# 4Z_PCB_2.net
KiCad netlist of a schematic drawn in Altium Designer
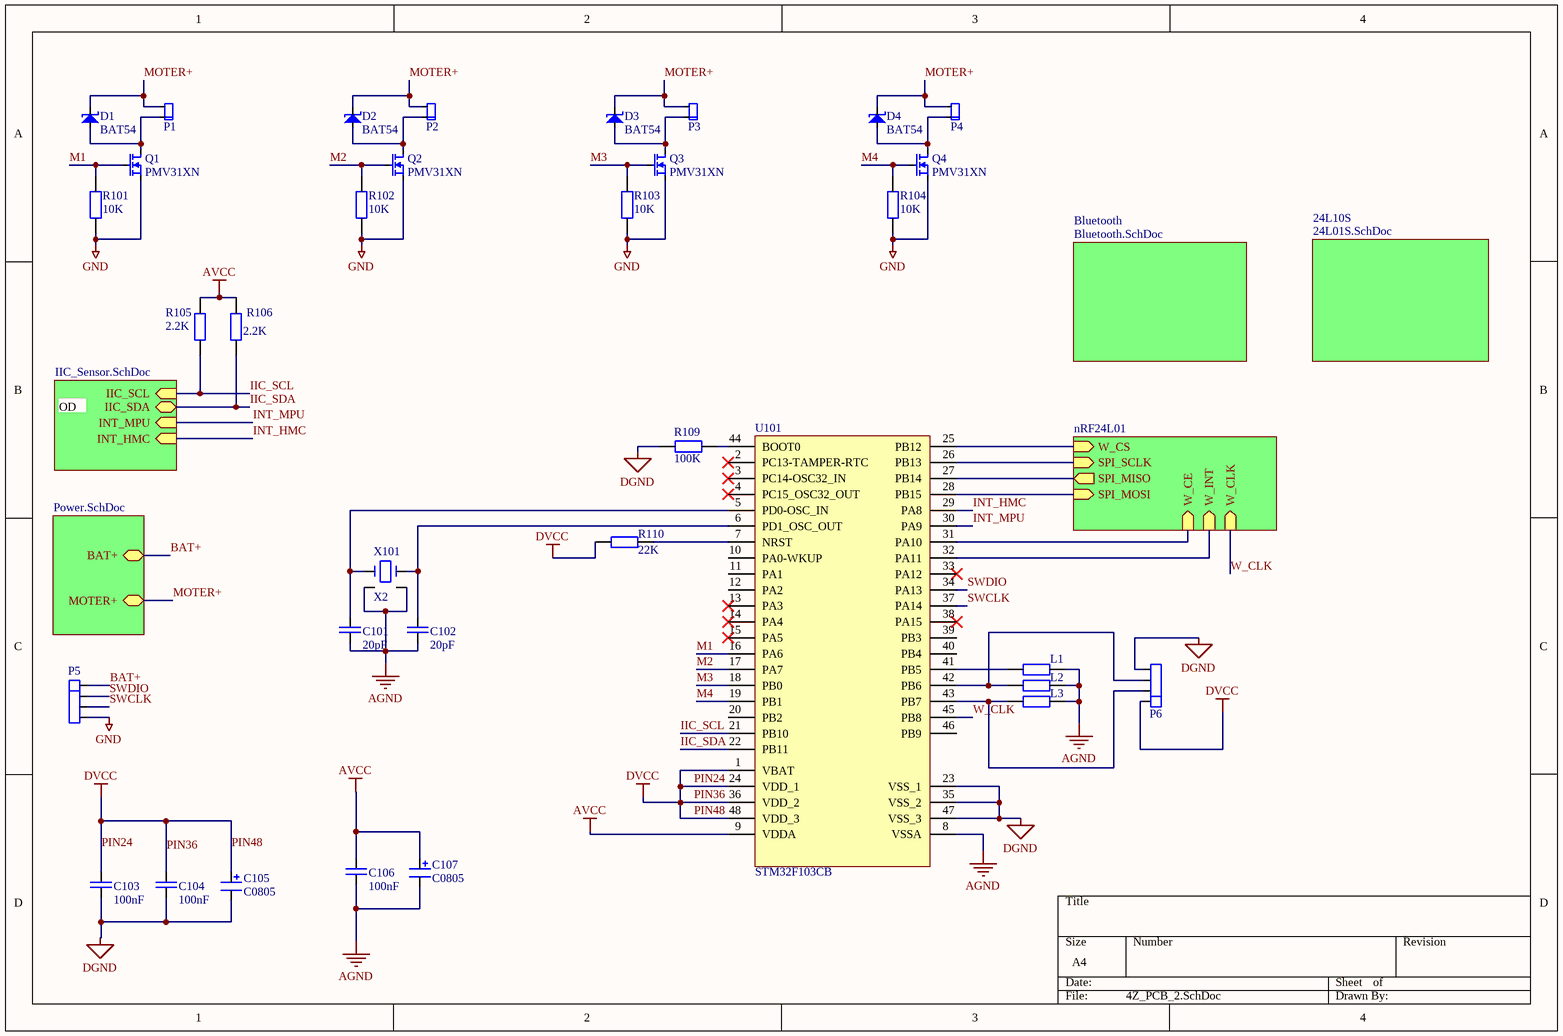
[diagram p0: 4Z_PCB_2.SchDoc]

(export (version "E")
  (design (tool "Eeschema 10.0.6"))
  (components
    (comp (ref "C101") (value "20pF") (footprint "0603") (libsource (lib "Library") (part "C0603")))
    (comp (ref "C102") (value "20pF") (footprint "0603") (libsource (lib "Library") (part "C0603")))
    (comp (ref "C103") (value "100nF") (footprint "0603") (libsource (lib "Library") (part "C0603")))
    (comp (ref "C104") (value "100nF") (footprint "0603") (libsource (lib "Library") (part "C0603")))
    (comp (ref "C105") (value "C0805") (footprint "0805") (libsource (lib "Library") (part "C0805")))
    (comp (ref "C106") (value "100nF") (footprint "0603") (libsource (lib "Library") (part "C0603")))
    (comp (ref "C107") (value "C0805") (footprint "0805") (libsource (lib "Library") (part "C0805")))
    (comp (ref "D1") (value "BAT54") (footprint "BAT54") (libsource (lib "Library") (part "BAT54")))
    (comp (ref "D2") (value "BAT54") (footprint "BAT54") (libsource (lib "Library") (part "BAT54")))
    (comp (ref "D3") (value "BAT54") (footprint "BAT54") (libsource (lib "Library") (part "BAT54")))
    (comp (ref "D4") (value "BAT54") (footprint "BAT54") (libsource (lib "Library") (part "BAT54")))
    (comp (ref "L1") (value "~") (footprint "0603") (libsource (lib "Library") (part "R0603")))
    (comp (ref "L2") (value "~") (footprint "0603") (libsource (lib "Library") (part "R0603")))
    (comp (ref "L3") (value "~") (footprint "0603") (libsource (lib "Library") (part "R0603")))
    (comp (ref "P1") (value "DIP_2") (footprint "DIP_2") (libsource (lib "Library") (part "DIP_2")))
    (comp (ref "P2") (value "DIP_2") (footprint "DIP_2") (libsource (lib "Library") (part "DIP_2")))
    (comp (ref "P3") (value "DIP_2") (footprint "DIP_2") (libsource (lib "Library") (part "DIP_2")))
    (comp (ref "P4") (value "DIP_2") (footprint "DIP_2") (libsource (lib "Library") (part "DIP_2")))
    (comp (ref "P5") (value "DIP_4") (footprint "DIP_4") (libsource (lib "Library") (part "DIP_4")))
    (comp (ref "P6") (value "~") (footprint "DIP_4") (libsource (lib "Library") (part "DIP_4")))
    (comp (ref "Q1")
      (value "PMV31XN")
      (footprint "SOT23-TO236AB")
      (libsource (lib "Library") (part "PMV31XN"))
    )
    (comp (ref "Q2")
      (value "PMV31XN")
      (footprint "SOT23-TO236AB")
      (libsource (lib "Library") (part "PMV31XN"))
    )
    (comp (ref "Q3")
      (value "PMV31XN")
      (footprint "SOT23-TO236AB")
      (libsource (lib "Library") (part "PMV31XN"))
    )
    (comp (ref "Q4")
      (value "PMV31XN")
      (footprint "SOT23-TO236AB")
      (libsource (lib "Library") (part "PMV31XN"))
    )
    (comp (ref "R101") (value "10K") (footprint "0603") (libsource (lib "Library") (part "R0603")))
    (comp (ref "R102") (value "10K") (footprint "0603") (libsource (lib "Library") (part "R0603")))
    (comp (ref "R103") (value "10K") (footprint "0603") (libsource (lib "Library") (part "R0603")))
    (comp (ref "R104") (value "10K") (footprint "0603") (libsource (lib "Library") (part "R0603")))
    (comp (ref "R105") (value "2.2K") (footprint "0603") (libsource (lib "Library") (part "R0603")))
    (comp (ref "R106") (value "2.2K") (footprint "0603") (libsource (lib "Library") (part "R0603")))
    (comp (ref "R109") (value "100K") (footprint "0603") (libsource (lib "Library") (part "R0603")))
    (comp (ref "R110") (value "22K") (footprint "0603") (libsource (lib "Library") (part "R0603")))
    (comp (ref "U101")
      (value "STM32F103CB")
      (footprint "LQFP48")
      (libsource (lib "Library") (part "STM32F103CB"))
    )
    (comp (ref "X101")
      (value "X2")
      (footprint "3225")
      (description "3225")
      (libsource (lib "Library") (part "X2"))
    )
  )
  (nets
    (net (code "1") (name "/BAT+") (class "Default")
      (node (ref "P5") (pin "1") (pinfunction "1_1") (pintype "passive"))
    )
    (net (code "2") (name "/IIC_SCL") (class "Default")
      (node (ref "R105") (pin "2") (pinfunction "2_2") (pintype "passive"))
      (node (ref "U101") (pin "21") (pinfunction "PB10_21") (pintype "passive"))
    )
    (net (code "3") (name "/IIC_SDA") (class "Default")
      (node (ref "R106") (pin "2") (pinfunction "2_2") (pintype "passive"))
      (node (ref "U101") (pin "22") (pinfunction "PB11_22") (pintype "passive"))
    )
    (net (code "4") (name "/INT_HMC") (class "Default")
      (node (ref "U101") (pin "29") (pinfunction "PA8_29") (pintype "passive"))
    )
    (net (code "5") (name "/INT_MPU") (class "Default")
      (node (ref "U101") (pin "30") (pinfunction "PA9_30") (pintype "passive"))
    )
    (net (code "6") (name "/M1") (class "Default")
      (node (ref "Q1") (pin "1") (pinfunction "1_1") (pintype "passive"))
      (node (ref "R101") (pin "1") (pinfunction "1_1") (pintype "passive"))
      (node (ref "U101") (pin "16") (pinfunction "PA6_16") (pintype "passive"))
    )
    (net (code "7") (name "/M2") (class "Default")
      (node (ref "Q2") (pin "1") (pinfunction "1_1") (pintype "passive"))
      (node (ref "R102") (pin "1") (pinfunction "1_1") (pintype "passive"))
      (node (ref "U101") (pin "17") (pinfunction "PA7_17") (pintype "passive"))
    )
    (net (code "8") (name "/M3") (class "Default")
      (node (ref "Q3") (pin "1") (pinfunction "1_1") (pintype "passive"))
      (node (ref "R103") (pin "1") (pinfunction "1_1") (pintype "passive"))
      (node (ref "U101") (pin "18") (pinfunction "PB0_18") (pintype "passive"))
    )
    (net (code "9") (name "/M4") (class "Default")
      (node (ref "Q4") (pin "1") (pinfunction "1_1") (pintype "passive"))
      (node (ref "R104") (pin "1") (pinfunction "1_1") (pintype "passive"))
      (node (ref "U101") (pin "19") (pinfunction "PB1_19") (pintype "passive"))
    )
    (net (code "10") (name "/MOTER+") (class "Default")
      (node (ref "D1") (pin "3") (pinfunction "3_3") (pintype "passive"))
      (node (ref "D2") (pin "3") (pinfunction "3_3") (pintype "passive"))
      (node (ref "D3") (pin "3") (pinfunction "3_3") (pintype "passive"))
      (node (ref "D4") (pin "3") (pinfunction "3_3") (pintype "passive"))
      (node (ref "P1") (pin "2") (pinfunction "2_2") (pintype "passive"))
      (node (ref "P2") (pin "2") (pinfunction "2_2") (pintype "passive"))
      (node (ref "P3") (pin "2") (pinfunction "2_2") (pintype "passive"))
      (node (ref "P4") (pin "2") (pinfunction "2_2") (pintype "passive"))
    )
    (net (code "11") (name "/SPI_MISO") (class "Default")
      (node (ref "U101") (pin "27") (pinfunction "PB14_27") (pintype "passive"))
    )
    (net (code "12") (name "/SPI_MOSI") (class "Default")
      (node (ref "U101") (pin "28") (pinfunction "PB15_28") (pintype "passive"))
    )
    (net (code "13") (name "/SPI_SCLK") (class "Default")
      (node (ref "U101") (pin "26") (pinfunction "PB13_26") (pintype "passive"))
    )
    (net (code "14") (name "/SWCLK") (class "Default")
      (node (ref "P5") (pin "3") (pinfunction "3_3") (pintype "passive"))
      (node (ref "U101") (pin "37") (pinfunction "PA14_37") (pintype "passive"))
    )
    (net (code "15") (name "/SWDIO") (class "Default")
      (node (ref "P5") (pin "2") (pinfunction "2_2") (pintype "passive"))
      (node (ref "U101") (pin "34") (pinfunction "PA13_34") (pintype "passive"))
    )
    (net (code "16") (name "/W_CE") (class "Default")
      (node (ref "U101") (pin "31") (pinfunction "PA10_31") (pintype "passive"))
    )
    (net (code "17") (name "/W_CLK") (class "Default")
      (node (ref "U101") (pin "45") (pinfunction "PB8_45") (pintype "passive"))
    )
    (net (code "19") (name "/W_CS") (class "Default")
      (node (ref "U101") (pin "25") (pinfunction "PB12_25") (pintype "passive"))
    )
    (net (code "20") (name "/W_INT") (class "Default")
      (node (ref "U101") (pin "32") (pinfunction "PA11_32") (pintype "passive"))
    )
    (net (code "21") (name "AGND") (class "Default")
      (node (ref "C101") (pin "1") (pinfunction "1_1") (pintype "passive"))
      (node (ref "C102") (pin "1") (pinfunction "1_1") (pintype "passive"))
      (node (ref "C106") (pin "1") (pinfunction "1_1") (pintype "passive"))
      (node (ref "C107") (pin "2") (pinfunction "2_2") (pintype "passive"))
      (node (ref "L1") (pin "1") (pinfunction "1_1") (pintype "passive"))
      (node (ref "L2") (pin "1") (pinfunction "1_1") (pintype "passive"))
      (node (ref "L3") (pin "1") (pinfunction "1_1") (pintype "passive"))
      (node (ref "U101") (pin "8") (pinfunction "VSSA_8") (pintype "passive"))
      (node (ref "X101") (pin "2") (pinfunction "2_2") (pintype "passive"))
      (node (ref "X101") (pin "4") (pinfunction "4_4") (pintype "passive"))
    )
    (net (code "22") (name "AVCC") (class "Default")
      (node (ref "C106") (pin "2") (pinfunction "2_2") (pintype "passive"))
      (node (ref "C107") (pin "1") (pinfunction "1_1") (pintype "passive"))
      (node (ref "R105") (pin "1") (pinfunction "1_1") (pintype "passive"))
      (node (ref "R106") (pin "1") (pinfunction "1_1") (pintype "passive"))
      (node (ref "U101") (pin "9") (pinfunction "VDDA_9") (pintype "passive"))
    )
    (net (code "23") (name "DGND") (class "Default")
      (node (ref "C103") (pin "1") (pinfunction "1_1") (pintype "passive"))
      (node (ref "C104") (pin "1") (pinfunction "1_1") (pintype "passive"))
      (node (ref "C105") (pin "2") (pinfunction "2_2") (pintype "passive"))
      (node (ref "P6") (pin "4") (pinfunction "4_4") (pintype "passive"))
      (node (ref "R109") (pin "2") (pinfunction "2_2") (pintype "passive"))
      (node (ref "U101") (pin "23") (pinfunction "VSS_1_23") (pintype "passive"))
      (node (ref "U101") (pin "35") (pinfunction "VSS_2_35") (pintype "passive"))
      (node (ref "U101") (pin "47") (pinfunction "VSS_3_47") (pintype "passive"))
    )
    (net (code "24") (name "DVCC") (class "Default")
      (node (ref "C103") (pin "2") (pinfunction "2_2") (pintype "passive"))
      (node (ref "C104") (pin "2") (pinfunction "2_2") (pintype "passive"))
      (node (ref "C105") (pin "1") (pinfunction "1_1") (pintype "passive"))
      (node (ref "P6") (pin "1") (pinfunction "1_1") (pintype "passive"))
      (node (ref "R110") (pin "2") (pinfunction "2_2") (pintype "passive"))
      (node (ref "U101") (pin "1") (pinfunction "VBAT_1") (pintype "passive"))
      (node (ref "U101") (pin "24") (pinfunction "VDD_1_24") (pintype "passive"))
      (node (ref "U101") (pin "36") (pinfunction "VDD_2_36") (pintype "passive"))
      (node (ref "U101") (pin "48") (pinfunction "VDD_3_48") (pintype "passive"))
    )
    (net (code "25") (name "GND") (class "Default")
      (node (ref "P5") (pin "4") (pinfunction "4_4") (pintype "passive"))
      (node (ref "Q1") (pin "2") (pinfunction "2_2") (pintype "passive"))
      (node (ref "Q2") (pin "2") (pinfunction "2_2") (pintype "passive"))
      (node (ref "Q3") (pin "2") (pinfunction "2_2") (pintype "passive"))
      (node (ref "Q4") (pin "2") (pinfunction "2_2") (pintype "passive"))
      (node (ref "R101") (pin "2") (pinfunction "2_2") (pintype "passive"))
      (node (ref "R102") (pin "2") (pinfunction "2_2") (pintype "passive"))
      (node (ref "R103") (pin "2") (pinfunction "2_2") (pintype "passive"))
      (node (ref "R104") (pin "2") (pinfunction "2_2") (pintype "passive"))
    )
    (net (code "26") (name "Net-(D1-Pad1)") (class "Default")
      (node (ref "D1") (pin "1") (pinfunction "1_1") (pintype "passive"))
      (node (ref "P1") (pin "1") (pinfunction "1_1") (pintype "passive"))
      (node (ref "Q1") (pin "3") (pinfunction "3_3") (pintype "passive"))
    )
    (net (code "27") (name "Net-(D2-Pad1)") (class "Default")
      (node (ref "D2") (pin "1") (pinfunction "1_1") (pintype "passive"))
      (node (ref "P2") (pin "1") (pinfunction "1_1") (pintype "passive"))
      (node (ref "Q2") (pin "3") (pinfunction "3_3") (pintype "passive"))
    )
    (net (code "28") (name "Net-(D3-Pad1)") (class "Default")
      (node (ref "D3") (pin "1") (pinfunction "1_1") (pintype "passive"))
      (node (ref "P3") (pin "1") (pinfunction "1_1") (pintype "passive"))
      (node (ref "Q3") (pin "3") (pinfunction "3_3") (pintype "passive"))
    )
    (net (code "29") (name "Net-(D4-Pad1)") (class "Default")
      (node (ref "D4") (pin "1") (pinfunction "1_1") (pintype "passive"))
      (node (ref "P4") (pin "1") (pinfunction "1_1") (pintype "passive"))
      (node (ref "Q4") (pin "3") (pinfunction "3_3") (pintype "passive"))
    )
    (net (code "30") (name "Net-(U101-BOOT0)") (class "Default")
      (node (ref "R109") (pin "1") (pinfunction "1_1") (pintype "passive"))
      (node (ref "U101") (pin "44") (pinfunction "BOOT0_44") (pintype "passive"))
    )
    (net (code "31") (name "Net-(U101-NRST)") (class "Default")
      (node (ref "R110") (pin "1") (pinfunction "1_1") (pintype "passive"))
      (node (ref "U101") (pin "7") (pinfunction "NRST_7") (pintype "passive"))
    )
    (net (code "32") (name "Net-(U101-PB5)") (class "Default")
      (node (ref "L1") (pin "2") (pinfunction "2_2") (pintype "passive"))
      (node (ref "U101") (pin "41") (pinfunction "PB5_41") (pintype "passive"))
    )
    (net (code "33") (name "Net-(U101-PB6)") (class "Default")
      (node (ref "L2") (pin "2") (pinfunction "2_2") (pintype "passive"))
      (node (ref "P6") (pin "3") (pinfunction "3_3") (pintype "passive"))
      (node (ref "U101") (pin "42") (pinfunction "PB6_42") (pintype "passive"))
    )
    (net (code "34") (name "Net-(U101-PB7)") (class "Default")
      (node (ref "L3") (pin "2") (pinfunction "2_2") (pintype "passive"))
      (node (ref "P6") (pin "2") (pinfunction "2_2") (pintype "passive"))
      (node (ref "U101") (pin "43") (pinfunction "PB7_43") (pintype "passive"))
    )
    (net (code "35") (name "Net-(U101-PD0-OSC_IN)") (class "Default")
      (node (ref "C101") (pin "2") (pinfunction "2_2") (pintype "passive"))
      (node (ref "U101") (pin "5") (pinfunction "PD0-OSC_IN_5") (pintype "passive"))
      (node (ref "X101") (pin "1") (pintype "passive"))
    )
    (net (code "36") (name "Net-(U101-PD1_OSC_OUT)") (class "Default")
      (node (ref "C102") (pin "2") (pinfunction "2_2") (pintype "passive"))
      (node (ref "U101") (pin "6") (pinfunction "PD1_OSC_OUT_6") (pintype "passive"))
      (node (ref "X101") (pin "3") (pintype "passive"))
    )
    (net (code "37") (name "unconnected-(U101-PA0-WKUP-Pad10)") (class "Default")
      (node (ref "U101") (pin "10") (pinfunction "PA0-WKUP_10") (pintype "passive"))
    )
    (net (code "38") (name "unconnected-(U101-PA1-Pad11)") (class "Default")
      (node (ref "U101") (pin "11") (pinfunction "PA1_11") (pintype "passive"))
    )
    (net (code "39") (name "unconnected-(U101-PA2-Pad12)") (class "Default")
      (node (ref "U101") (pin "12") (pinfunction "PA2_12") (pintype "passive"))
    )
    (net (code "40") (name "unconnected-(U101-PA3-Pad13)") (class "Default")
      (node (ref "U101") (pin "13") (pinfunction "PA3_13") (pintype "passive+no_connect"))
    )
    (net (code "41") (name "unconnected-(U101-PA4-Pad14)") (class "Default")
      (node (ref "U101") (pin "14") (pinfunction "PA4_14") (pintype "passive+no_connect"))
    )
    (net (code "42") (name "unconnected-(U101-PA5-Pad15)") (class "Default")
      (node (ref "U101") (pin "15") (pinfunction "PA5_15") (pintype "passive+no_connect"))
    )
    (net (code "43") (name "unconnected-(U101-PA12-Pad33)") (class "Default")
      (node (ref "U101") (pin "33") (pinfunction "PA12_33") (pintype "passive+no_connect"))
    )
    (net (code "44") (name "unconnected-(U101-PA15-Pad38)") (class "Default")
      (node (ref "U101") (pin "38") (pinfunction "PA15_38") (pintype "passive+no_connect"))
    )
    (net (code "45") (name "unconnected-(U101-PB2-Pad20)") (class "Default")
      (node (ref "U101") (pin "20") (pinfunction "PB2_20") (pintype "passive"))
    )
    (net (code "46") (name "unconnected-(U101-PB3-Pad39)") (class "Default")
      (node (ref "U101") (pin "39") (pinfunction "PB3_39") (pintype "passive"))
    )
    (net (code "47") (name "unconnected-(U101-PB4-Pad40)") (class "Default")
      (node (ref "U101") (pin "40") (pinfunction "PB4_40") (pintype "passive"))
    )
    (net (code "48") (name "unconnected-(U101-PB9-Pad46)") (class "Default")
      (node (ref "U101") (pin "46") (pinfunction "PB9_46") (pintype "passive"))
    )
    (net (code "49") (name "unconnected-(U101-PC13-TAMPER-RTC-Pad2)") (class "Default")
      (node (ref "U101") (pin "2") (pinfunction "PC13-TAMPER-RTC_2") (pintype "passive+no_connect"))
    )
    (net (code "50") (name "unconnected-(U101-PC14-OSC32_IN-Pad3)") (class "Default")
      (node (ref "U101") (pin "3") (pinfunction "PC14-OSC32_IN_3") (pintype "passive+no_connect"))
    )
    (net (code "51") (name "unconnected-(U101-PC15_OSC32_OUT-Pad4)") (class "Default")
      (node (ref "U101") (pin "4") (pinfunction "PC15_OSC32_OUT_4") (pintype "passive+no_connect"))
    )
  )
)
